# ReboostV2_Bridge.net
KiCad netlist of a schematic drawn in Altium Designer
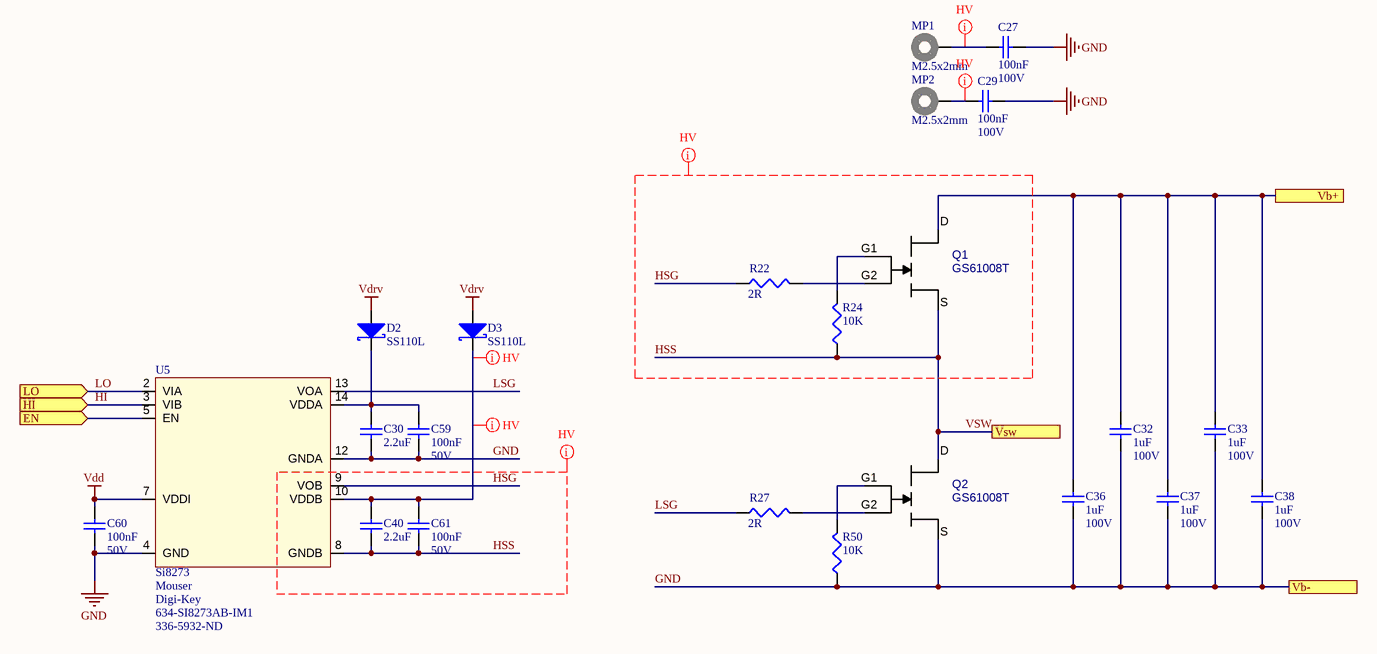
[diagram p0: ReboostV2_Bridge.SchDoc]

(export (version "E")
  (design (tool "Eeschema 10.0.6"))
  (components
    (comp (ref "C27")
      (value "100nF")
      (footprint "C-0805")
      (description "Capacitor, 100nF, 100V, X7R")
      (fields
        (field (name "VOLTAGE RATING") "100V")
        (field (name "MANUFACTURER") "KEMET")
        (field (name "MANUFACTURER PART NUMBER") "C0805C104K1RACTU")
      )
      (libsource (lib "Reboostv2") (part "100nF/0805/CER/100V"))
    )
    (comp (ref "C29")
      (value "100nF")
      (footprint "C-0805")
      (description "Capacitor, 100nF, 100V, X7R")
      (fields
        (field (name "VOLTAGE RATING") "100V")
        (field (name "MANUFACTURER") "KEMET")
        (field (name "MANUFACTURER PART NUMBER") "C0805C104K1RACTU")
      )
      (libsource (lib "Reboostv2") (part "100nF/0805/CER/100V"))
    )
    (comp (ref "C30")
      (value "2.2uF")
      (footprint "C0603")
      (description "Capacitor, 2.2uF, 16V, X5R")
      (fields
        (field (name "MANUFACTURER") "MURATA")
        (field (name "MANUFACTURER PART NUMBER") "GRM188R61C225KE15D")
      )
      (libsource (lib "Reboostv2") (part "2.2uF/0603/CER/16V"))
    )
    (comp (ref "C32")
      (value "1uF")
      (footprint "C-1206")
      (description "Capacitor, 1uF, 100V, X7R")
      (fields
        (field (name "VOLTAGE RATING") "100V")
        (field (name "MANUFACTURER") "AVX")
        (field (name "MANUFACTURER PART NUMBER") "12061C105K4Z2A")
      )
      (libsource (lib "Reboostv2") (part "1uF/1206/CER/100V"))
    )
    (comp (ref "C33")
      (value "1uF")
      (footprint "C-1206")
      (description "Capacitor, 1uF, 100V, X7R")
      (fields
        (field (name "VOLTAGE RATING") "100V")
        (field (name "MANUFACTURER") "AVX")
        (field (name "MANUFACTURER PART NUMBER") "12061C105K4Z2A")
      )
      (libsource (lib "Reboostv2") (part "1uF/1206/CER/100V"))
    )
    (comp (ref "C36")
      (value "1uF")
      (footprint "C-1206")
      (description "Capacitor, 1uF, 100V, X7R")
      (fields
        (field (name "VOLTAGE RATING") "100V")
        (field (name "MANUFACTURER") "AVX")
        (field (name "MANUFACTURER PART NUMBER") "12061C105K4Z2A")
      )
      (libsource (lib "Reboostv2") (part "1uF/1206/CER/100V"))
    )
    (comp (ref "C37")
      (value "1uF")
      (footprint "C-1206")
      (description "Capacitor, 1uF, 100V, X7R")
      (fields
        (field (name "VOLTAGE RATING") "100V")
        (field (name "MANUFACTURER") "AVX")
        (field (name "MANUFACTURER PART NUMBER") "12061C105K4Z2A")
      )
      (libsource (lib "Reboostv2") (part "1uF/1206/CER/100V"))
    )
    (comp (ref "C38")
      (value "1uF")
      (footprint "C-1206")
      (description "Capacitor, 1uF, 100V, X7R")
      (fields
        (field (name "VOLTAGE RATING") "100V")
        (field (name "MANUFACTURER") "AVX")
        (field (name "MANUFACTURER PART NUMBER") "12061C105K4Z2A")
      )
      (libsource (lib "Reboostv2") (part "1uF/1206/CER/100V"))
    )
    (comp (ref "C40")
      (value "2.2uF")
      (footprint "C0603")
      (description "Capacitor, 2.2uF, 16V, X5R")
      (fields
        (field (name "MANUFACTURER") "MURATA")
        (field (name "MANUFACTURER PART NUMBER") "GRM188R61C225KE15D")
      )
      (libsource (lib "Reboostv2") (part "2.2uF/0603/CER/16V"))
    )
    (comp (ref "C59")
      (value "100nF")
      (footprint "C0603")
      (description "Capacitor, 100nF, 50V, X7R")
      (fields
        (field (name "VOLTAGE RATING") "50V")
        (field (name "MANUFACTURER") "MULTICOMP")
        (field (name "MANUFACTURER PART NUMBER") "MCCA000255")
      )
      (libsource (lib "Reboostv2") (part "100nF/0603/CER/50V"))
    )
    (comp (ref "C60")
      (value "100nF")
      (footprint "C0603")
      (description "Capacitor, 100nF, 50V, X7R")
      (fields
        (field (name "VOLTAGE RATING") "50V")
        (field (name "MANUFACTURER") "MULTICOMP")
        (field (name "MANUFACTURER PART NUMBER") "MCCA000255")
      )
      (libsource (lib "Reboostv2") (part "100nF/0603/CER/50V"))
    )
    (comp (ref "C61")
      (value "100nF")
      (footprint "C0603")
      (description "Capacitor, 100nF, 50V, X7R")
      (fields
        (field (name "VOLTAGE RATING") "50V")
        (field (name "MANUFACTURER") "MULTICOMP")
        (field (name "MANUFACTURER PART NUMBER") "MCCA000255")
      )
      (libsource (lib "Reboostv2") (part "100nF/0603/CER/50V"))
    )
    (comp (ref "D2")
      (value "SS110L")
      (footprint "SUB-SMA")
      (description "Diode Schottky, Vrrm: 100V, If: 1A, Vf: 0.9V")
      (fields
        (field (name "MANUFACTURER") "TAIWAN SEMICONDUCTOR")
        (field (name "MANUFACTURER PART NUMBER") "SS110L R3")
      )
      (libsource (lib "Reboostv2") (part "SS110L"))
    )
    (comp (ref "D3")
      (value "SS110L")
      (footprint "SUB-SMA")
      (description "Diode Schottky, Vrrm: 100V, If: 1A, Vf: 0.9V")
      (fields
        (field (name "MANUFACTURER") "TAIWAN SEMICONDUCTOR")
        (field (name "MANUFACTURER PART NUMBER") "SS110L R3")
      )
      (libsource (lib "Reboostv2") (part "SS110L"))
    )
    (comp (ref "MP1")
      (value "M2.5x2mm")
      (footprint "9774020151")
      (description "WA-SMSI SMT Steel Spacer, M2.5 Thread Internal, OD 5.1mm, M2.5x2mm")
      (fields
        (field (name "MANUFACTURER PART NUMBER") "9774020151")
        (field (name "MANUFACTURER") "Wurth Elektronik")
      )
      (libsource (lib "Reboostv2") (part "9774020151"))
    )
    (comp (ref "MP2")
      (value "M2.5x2mm")
      (footprint "9774020151")
      (description "WA-SMSI SMT Steel Spacer, M2.5 Thread Internal, OD 5.1mm, M2.5x2mm")
      (fields
        (field (name "MANUFACTURER PART NUMBER") "9774020151")
        (field (name "MANUFACTURER") "Wurth Elektronik")
      )
      (libsource (lib "Reboostv2") (part "9774020151"))
    )
    (comp (ref "Q1")
      (value "GS61008T")
      (footprint "GS61008T")
      (description "GAN TRANS E-MODE 100V 90A TOP SIDE COOL")
      (fields (field (name "MANUFACTURER") "GaN Systems"))
      (libsource (lib "Reboostv2") (part "GS61008T"))
    )
    (comp (ref "Q2")
      (value "GS61008T")
      (footprint "GS61008T")
      (description "GAN TRANS E-MODE 100V 90A TOP SIDE COOL")
      (fields (field (name "MANUFACTURER") "GaN Systems"))
      (libsource (lib "Reboostv2") (part "GS61008T"))
    )
    (comp (ref "R22")
      (value "2R")
      (footprint "0603")
      (description "Resistor, 2R, 5%, 0.1W, 75V, 200PPM, 0603")
      (fields
        (field (name "MANUFACTURER") "PANASONIC")
        (field (name "MANUFACTURER PART NUMBER") "ERJ3GEYJ2R0V")
      )
      (libsource (lib "Reboostv2") (part "2/0603/0100W/75V"))
    )
    (comp (ref "R24")
      (value "10K")
      (footprint "0603")
      (description "Resistor, 10K, 1%, 0.063W, 50V, 100PPM, 0603")
      (fields
        (field (name "MANUFACTURER") "VISHAY DRALORIC")
        (field (name "MANUFACTURER PART NUMBER") "CRCW060310K0FKEA")
      )
      (libsource (lib "Reboostv2") (part "10K/0603/0063W/50V"))
    )
    (comp (ref "R27")
      (value "2R")
      (footprint "0603")
      (description "Resistor, 2R, 5%, 0.1W, 75V, 200PPM, 0603")
      (fields
        (field (name "MANUFACTURER") "PANASONIC")
        (field (name "MANUFACTURER PART NUMBER") "ERJ3GEYJ2R0V")
      )
      (libsource (lib "Reboostv2") (part "2/0603/0100W/75V"))
    )
    (comp (ref "R50")
      (value "10K")
      (footprint "0603")
      (description "Resistor, 10K, 1%, 0.063W, 50V, 100PPM, 0603")
      (fields
        (field (name "MANUFACTURER") "VISHAY DRALORIC")
        (field (name "MANUFACTURER PART NUMBER") "CRCW060310K0FKEA")
      )
      (libsource (lib "Reboostv2") (part "10K/0603/0063W/50V"))
    )
    (comp (ref "U5")
      (value "Si8273")
      (footprint "DFN-14")
      (description "4 Amp ISOdriver with High Transient (dV/dt) Immunity")
      (fields
        (field (name "SUPPLIER 1") "Mouser")
        (field (name "SUPPLIER 2") "Digi-Key")
        (field (name "SUPPLIER PART NUMBER 1") "634-SI8273AB-IM1")
        (field (name "SUPPLIER PART NUMBER 2") "336-5932-ND")
        (field (name "MANUFACTURER") "Skyworks Solutions Inc.")
        (field (name "MPN") "SI8273AB-IM1")
      )
      (libsource (lib "Reboostv2") (part "Si8273ABIM1"))
    )
  )
  (nets
    (net (code "1") (name "/EN") (class "Default")
      (node (ref "U5") (pin "5") (pinfunction "EN_5") (pintype "passive"))
    )
    (net (code "2") (name "/HI") (class "Default")
      (node (ref "U5") (pin "3") (pinfunction "VIB_3") (pintype "passive"))
    )
    (net (code "3") (name "/HSG") (class "Default")
      (node (ref "R22") (pin "1") (pinfunction "1_1") (pintype "passive"))
      (node (ref "U5") (pin "9") (pinfunction "VOB_9") (pintype "passive"))
    )
    (net (code "4") (name "/HSS") (class "Default")
      (node (ref "C40") (pin "1") (pinfunction "1_1") (pintype "passive"))
      (node (ref "C61") (pin "1") (pinfunction "1_1") (pintype "passive"))
      (node (ref "Q1") (pin "S") (pinfunction "S_S") (pintype "passive"))
      (node (ref "Q2") (pin "D") (pinfunction "D_D") (pintype "passive"))
      (node (ref "R24") (pin "1") (pinfunction "1_1") (pintype "passive"))
      (node (ref "U5") (pin "8") (pinfunction "GNDB_8") (pintype "passive"))
    )
    (net (code "5") (name "/LO") (class "Default")
      (node (ref "U5") (pin "2") (pinfunction "VIA_2") (pintype "passive"))
    )
    (net (code "6") (name "/LSG") (class "Default")
      (node (ref "R27") (pin "1") (pinfunction "1_1") (pintype "passive"))
      (node (ref "U5") (pin "13") (pinfunction "VOA_13") (pintype "passive"))
    )
    (net (code "7") (name "/Vb+") (class "Default")
      (node (ref "C32") (pin "2") (pinfunction "2_2") (pintype "passive"))
      (node (ref "C33") (pin "2") (pinfunction "2_2") (pintype "passive"))
      (node (ref "C36") (pin "2") (pinfunction "2_2") (pintype "passive"))
      (node (ref "C37") (pin "2") (pinfunction "2_2") (pintype "passive"))
      (node (ref "C38") (pin "2") (pinfunction "2_2") (pintype "passive"))
      (node (ref "Q1") (pin "D") (pinfunction "D_D") (pintype "passive"))
    )
    (net (code "8") (name "GND") (class "Default")
      (node (ref "C27") (pin "1") (pinfunction "1_1") (pintype "passive"))
      (node (ref "C29") (pin "1") (pinfunction "1_1") (pintype "passive"))
      (node (ref "C30") (pin "1") (pinfunction "1_1") (pintype "passive"))
      (node (ref "C32") (pin "1") (pinfunction "1_1") (pintype "passive"))
      (node (ref "C33") (pin "1") (pinfunction "1_1") (pintype "passive"))
      (node (ref "C36") (pin "1") (pinfunction "1_1") (pintype "passive"))
      (node (ref "C37") (pin "1") (pinfunction "1_1") (pintype "passive"))
      (node (ref "C38") (pin "1") (pinfunction "1_1") (pintype "passive"))
      (node (ref "C59") (pin "1") (pinfunction "1_1") (pintype "passive"))
      (node (ref "C60") (pin "1") (pinfunction "1_1") (pintype "passive"))
      (node (ref "Q2") (pin "S") (pinfunction "S_S") (pintype "passive"))
      (node (ref "R50") (pin "1") (pinfunction "1_1") (pintype "passive"))
      (node (ref "U5") (pin "12") (pinfunction "GNDA_12") (pintype "passive"))
      (node (ref "U5") (pin "4") (pinfunction "GND_4") (pintype "passive"))
    )
    (net (code "9") (name "Net-(C27-Pad2)") (class "Default")
      (node (ref "C27") (pin "2") (pinfunction "2_2") (pintype "passive"))
      (node (ref "MP1") (pin "1") (pinfunction "1_1") (pintype "passive"))
    )
    (net (code "10") (name "Net-(C29-Pad2)") (class "Default")
      (node (ref "C29") (pin "2") (pinfunction "2_2") (pintype "passive"))
      (node (ref "MP2") (pin "1") (pinfunction "1_1") (pintype "passive"))
    )
    (net (code "11") (name "Net-(D2-K)") (class "Default")
      (node (ref "C30") (pin "2") (pinfunction "2_2") (pintype "passive"))
      (node (ref "C59") (pin "2") (pinfunction "2_2") (pintype "passive"))
      (node (ref "D2") (pin "2") (pinfunction "K_2") (pintype "passive"))
      (node (ref "U5") (pin "14") (pinfunction "VDDA_14") (pintype "passive"))
    )
    (net (code "12") (name "Net-(D3-K)") (class "Default")
      (node (ref "C40") (pin "2") (pinfunction "2_2") (pintype "passive"))
      (node (ref "C61") (pin "2") (pinfunction "2_2") (pintype "passive"))
      (node (ref "D3") (pin "2") (pinfunction "K_2") (pintype "passive"))
      (node (ref "U5") (pin "10") (pinfunction "VDDB_10") (pintype "passive"))
    )
    (net (code "13") (name "Net-(Q1-PadG1)") (class "Default")
      (node (ref "Q1") (pin "G1") (pinfunction "G1_G1") (pintype "passive"))
      (node (ref "R24") (pin "2") (pinfunction "2_2") (pintype "passive"))
    )
    (net (code "14") (name "Net-(Q1-PadG2)") (class "Default")
      (node (ref "Q1") (pin "G2") (pinfunction "G2_G2") (pintype "passive"))
      (node (ref "R22") (pin "2") (pinfunction "2_2") (pintype "passive"))
    )
    (net (code "15") (name "Net-(Q2-PadG1)") (class "Default")
      (node (ref "Q2") (pin "G1") (pinfunction "G1_G1") (pintype "passive"))
      (node (ref "R50") (pin "2") (pinfunction "2_2") (pintype "passive"))
    )
    (net (code "16") (name "Net-(Q2-PadG2)") (class "Default")
      (node (ref "Q2") (pin "G2") (pinfunction "G2_G2") (pintype "passive"))
      (node (ref "R27") (pin "2") (pinfunction "2_2") (pintype "passive"))
    )
    (net (code "17") (name "Vdd") (class "Default")
      (node (ref "C60") (pin "2") (pinfunction "2_2") (pintype "passive"))
      (node (ref "U5") (pin "7") (pinfunction "VDDI_7") (pintype "passive"))
    )
    (net (code "18") (name "Vdrv") (class "Default")
      (node (ref "D2") (pin "1") (pinfunction "A_1") (pintype "passive"))
      (node (ref "D3") (pin "1") (pinfunction "A_1") (pintype "passive"))
    )
  )
)
